# 03_-_MCU_and_Conn.net
KiCad netlist of a schematic drawn in Altium Designer
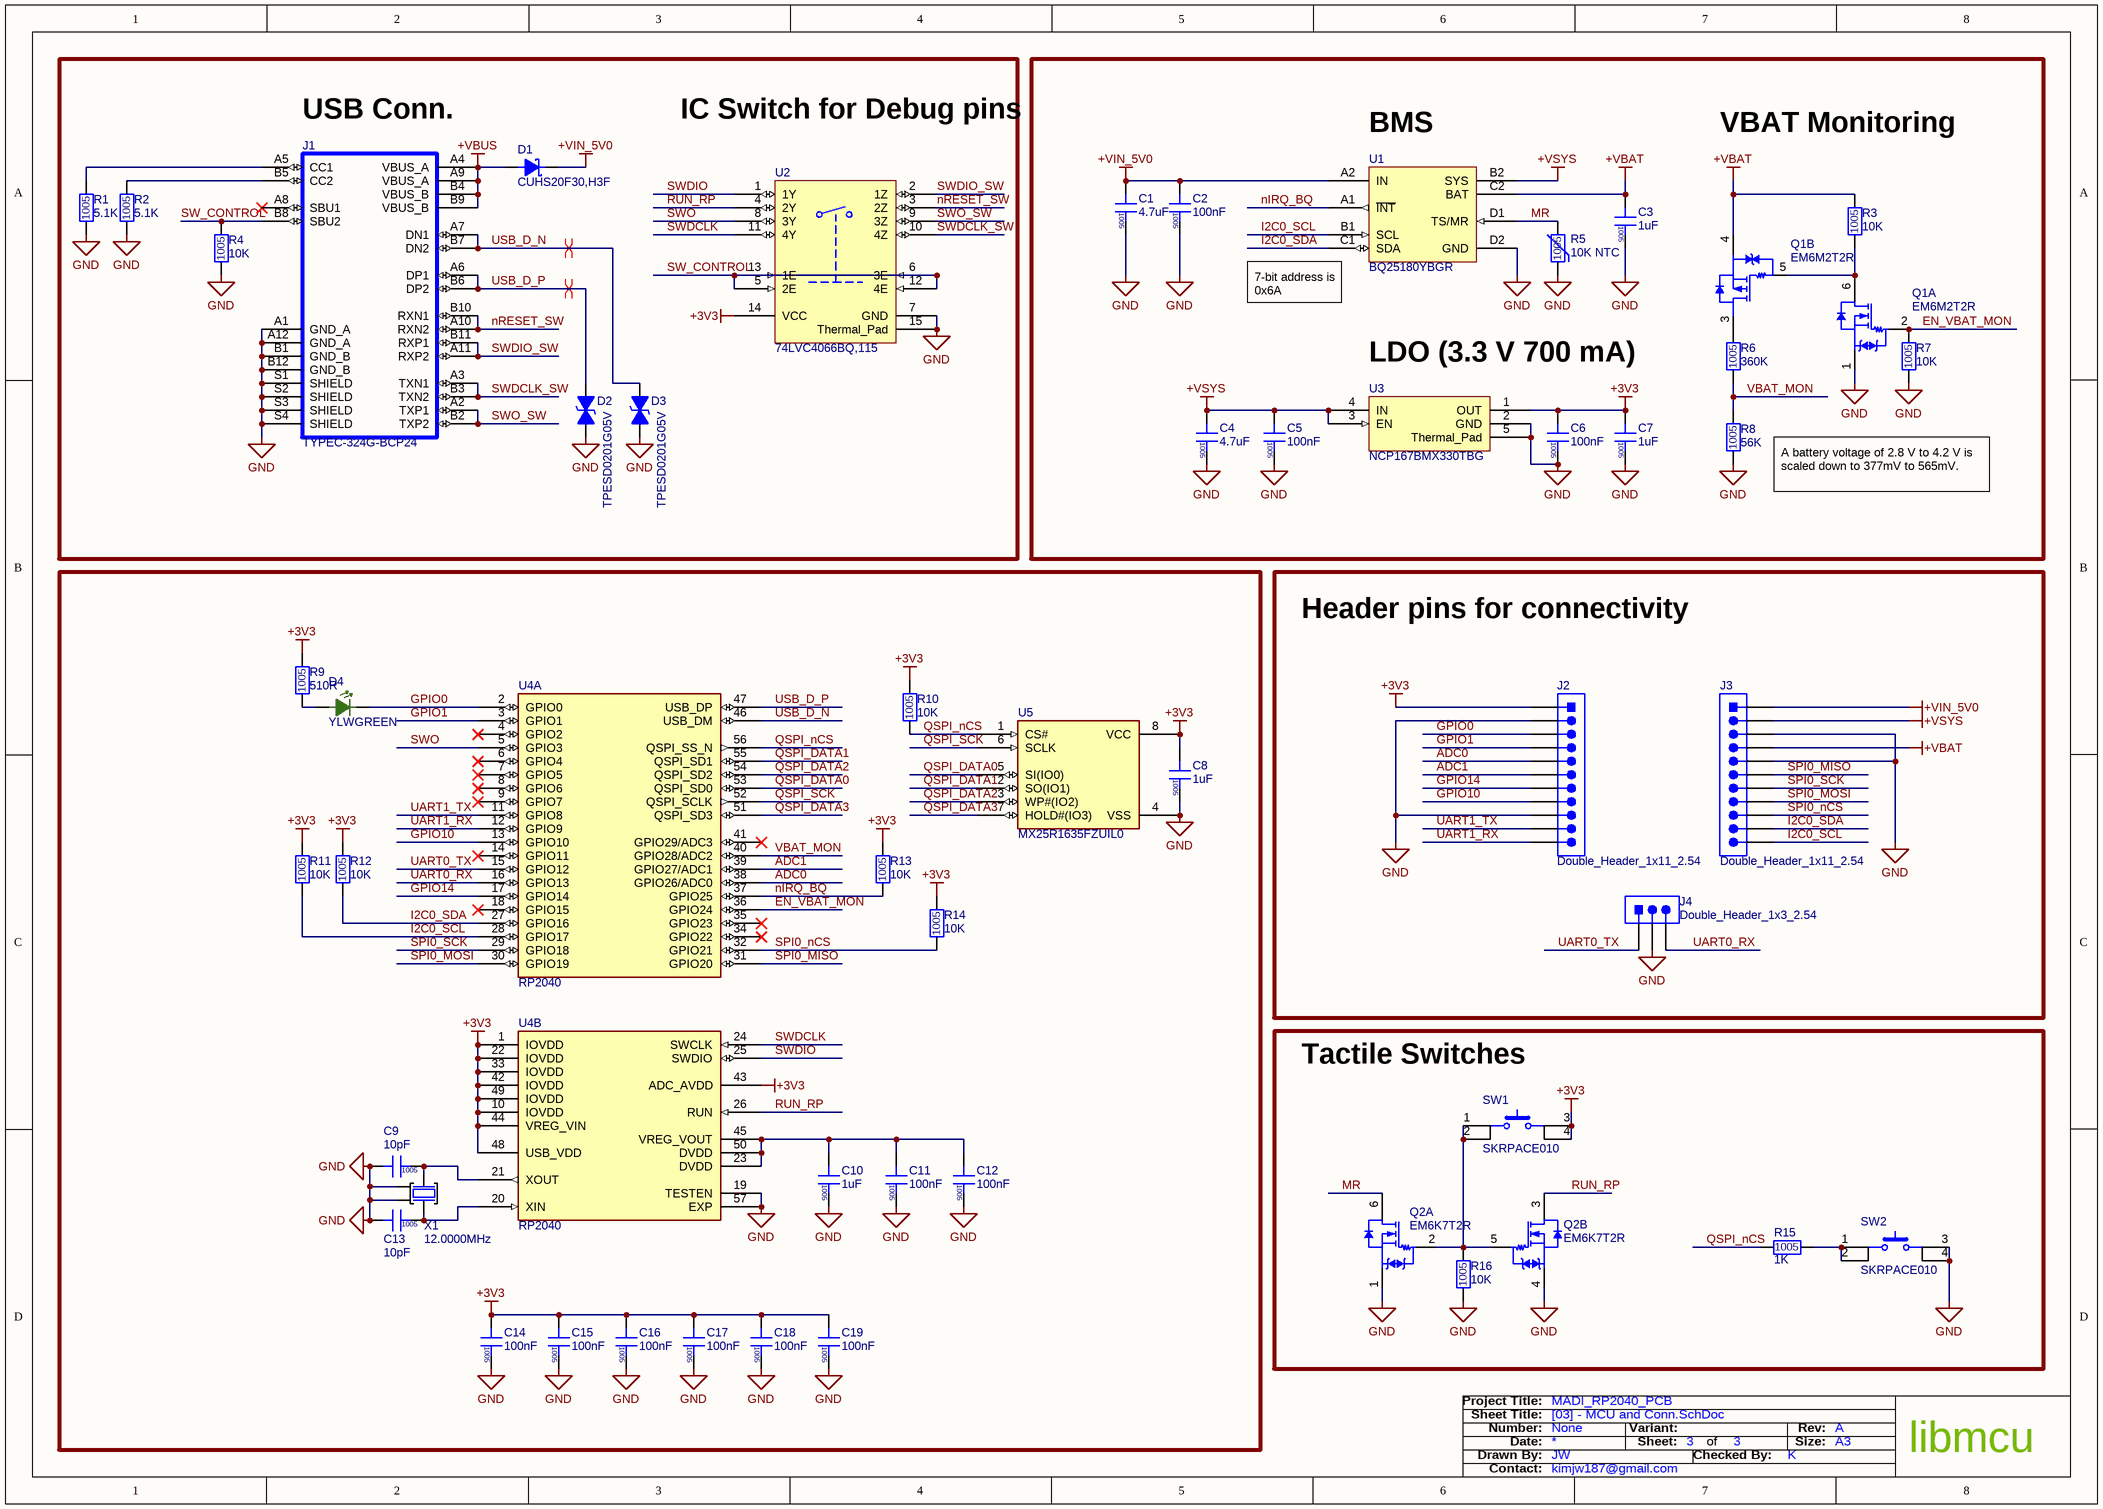
[diagram p0: [03] - MCU and Conn.SchDoc]

(export (version "E")
  (design (tool "Eeschema 10.0.6"))
  (components
    (comp (ref "C1")
      (value "4.7uF")
      (footprint "CAPC1005X06N")
      (description "CAP CER 4.7UF 10V X5R 0402")
      (fields
        (field (name "MANUFACTURER") "Samsung")
        (field (name "MANUFACTURER PART NUMBER") "CL05A475MP5NRNC")
      )
      (libsource (lib "Schlib-master") (part "CL05A475MP5NRNC"))
    )
    (comp (ref "C2")
      (value "100nF")
      (footprint "CAPC1005X06N")
      (description "CAP CER 0.1UF 16V X7R 0402")
      (fields
        (field (name "MANUFACTURER") "Samsung")
        (field (name "MANUFACTURER PART NUMBER") "CL05B104KO5NNNC")
      )
      (libsource (lib "Schlib-master") (part "CL05B104KO5NNNC"))
    )
    (comp (ref "C3")
      (value "1uF")
      (footprint "CAPC1005X06N")
      (description "CAP CER 1UF 16V X5R 0402")
      (fields
        (field (name "MANUFACTURER") "Samsung")
        (field (name "MANUFACTURER PART NUMBER") "CL05A105KO5NNNC")
      )
      (libsource (lib "Schlib-master") (part "CL05A105KO5NNNC"))
    )
    (comp (ref "C4")
      (value "4.7uF")
      (footprint "CAPC1005X06N")
      (description "CAP CER 4.7UF 10V X5R 0402")
      (fields
        (field (name "MANUFACTURER") "Samsung")
        (field (name "MANUFACTURER PART NUMBER") "CL05A475MP5NRNC")
      )
      (libsource (lib "Schlib-master") (part "CL05A475MP5NRNC"))
    )
    (comp (ref "C5")
      (value "100nF")
      (footprint "CAPC1005X06N")
      (description "CAP CER 0.1UF 16V X7R 0402")
      (fields
        (field (name "MANUFACTURER") "Samsung")
        (field (name "MANUFACTURER PART NUMBER") "CL05B104KO5NNNC")
      )
      (libsource (lib "Schlib-master") (part "CL05B104KO5NNNC"))
    )
    (comp (ref "C6")
      (value "100nF")
      (footprint "CAPC1005X06N")
      (description "CAP CER 0.1UF 16V X7R 0402")
      (fields
        (field (name "MANUFACTURER") "Samsung")
        (field (name "MANUFACTURER PART NUMBER") "CL05B104KO5NNNC")
      )
      (libsource (lib "Schlib-master") (part "CL05B104KO5NNNC"))
    )
    (comp (ref "C7")
      (value "1uF")
      (footprint "CAPC1005X06N")
      (description "CAP CER 1UF 16V X5R 0402")
      (fields
        (field (name "MANUFACTURER") "Samsung")
        (field (name "MANUFACTURER PART NUMBER") "CL05A105KO5NNNC")
      )
      (libsource (lib "Schlib-master") (part "CL05A105KO5NNNC"))
    )
    (comp (ref "C8")
      (value "1uF")
      (footprint "CAPC1005X06N")
      (description "CAP CER 1UF 16V X5R 0402")
      (fields
        (field (name "MANUFACTURER") "Samsung")
        (field (name "MANUFACTURER PART NUMBER") "CL05A105KO5NNNC")
      )
      (libsource (lib "Schlib-master") (part "CL05A105KO5NNNC"))
    )
    (comp (ref "C9")
      (value "10pF")
      (footprint "CAPC1005X06N")
      (description "CAP CER 10PF 50V C0G/NP0 0402")
      (fields
        (field (name "MANUFACTURER") "Samsung")
        (field (name "MANUFACTURER PART NUMBER") "CL05C100DB5NNNC")
      )
      (libsource (lib "Schlib-master") (part "CL05C100DB5NNNC"))
    )
    (comp (ref "C10")
      (value "1uF")
      (footprint "CAPC1005X06N")
      (description "CAP CER 1UF 16V X5R 0402")
      (fields
        (field (name "MANUFACTURER") "Samsung")
        (field (name "MANUFACTURER PART NUMBER") "CL05A105KO5NNNC")
      )
      (libsource (lib "Schlib-master") (part "CL05A105KO5NNNC"))
    )
    (comp (ref "C11")
      (value "100nF")
      (footprint "CAPC1005X06N")
      (description "CAP CER 0.1UF 16V X7R 0402")
      (fields
        (field (name "MANUFACTURER") "Samsung")
        (field (name "MANUFACTURER PART NUMBER") "CL05B104KO5NNNC")
      )
      (libsource (lib "Schlib-master") (part "CL05B104KO5NNNC"))
    )
    (comp (ref "C12")
      (value "100nF")
      (footprint "CAPC1005X06N")
      (description "CAP CER 0.1UF 16V X7R 0402")
      (fields
        (field (name "MANUFACTURER") "Samsung")
        (field (name "MANUFACTURER PART NUMBER") "CL05B104KO5NNNC")
      )
      (libsource (lib "Schlib-master") (part "CL05B104KO5NNNC"))
    )
    (comp (ref "C13")
      (value "10pF")
      (footprint "CAPC1005X06N")
      (description "CAP CER 10PF 50V C0G/NP0 0402")
      (fields
        (field (name "MANUFACTURER") "Samsung")
        (field (name "MANUFACTURER PART NUMBER") "CL05C100DB5NNNC")
      )
      (libsource (lib "Schlib-master") (part "CL05C100DB5NNNC"))
    )
    (comp (ref "C14")
      (value "100nF")
      (footprint "CAPC1005X06N")
      (description "CAP CER 0.1UF 16V X7R 0402")
      (fields
        (field (name "MANUFACTURER") "Samsung")
        (field (name "MANUFACTURER PART NUMBER") "CL05B104KO5NNNC")
      )
      (libsource (lib "Schlib-master") (part "CL05B104KO5NNNC"))
    )
    (comp (ref "C15")
      (value "100nF")
      (footprint "CAPC1005X06N")
      (description "CAP CER 0.1UF 16V X7R 0402")
      (fields
        (field (name "MANUFACTURER") "Samsung")
        (field (name "MANUFACTURER PART NUMBER") "CL05B104KO5NNNC")
      )
      (libsource (lib "Schlib-master") (part "CL05B104KO5NNNC"))
    )
    (comp (ref "C16")
      (value "100nF")
      (footprint "CAPC1005X06N")
      (description "CAP CER 0.1UF 16V X7R 0402")
      (fields
        (field (name "MANUFACTURER") "Samsung")
        (field (name "MANUFACTURER PART NUMBER") "CL05B104KO5NNNC")
      )
      (libsource (lib "Schlib-master") (part "CL05B104KO5NNNC"))
    )
    (comp (ref "C17")
      (value "100nF")
      (footprint "CAPC1005X06N")
      (description "CAP CER 0.1UF 16V X7R 0402")
      (fields
        (field (name "MANUFACTURER") "Samsung")
        (field (name "MANUFACTURER PART NUMBER") "CL05B104KO5NNNC")
      )
      (libsource (lib "Schlib-master") (part "CL05B104KO5NNNC"))
    )
    (comp (ref "C18")
      (value "100nF")
      (footprint "CAPC1005X06N")
      (description "CAP CER 0.1UF 16V X7R 0402")
      (fields
        (field (name "MANUFACTURER") "Samsung")
        (field (name "MANUFACTURER PART NUMBER") "CL05B104KO5NNNC")
      )
      (libsource (lib "Schlib-master") (part "CL05B104KO5NNNC"))
    )
    (comp (ref "C19")
      (value "100nF")
      (footprint "CAPC1005X06N")
      (description "CAP CER 0.1UF 16V X7R 0402")
      (fields
        (field (name "MANUFACTURER") "Samsung")
        (field (name "MANUFACTURER PART NUMBER") "CL05B104KO5NNNC")
      )
      (libsource (lib "Schlib-master") (part "CL05B104KO5NNNC"))
    )
    (comp (ref "D1")
      (value "CUHS20F30,H3F")
      (footprint "US2H-DIODE")
      (description "DIODE SCHOTTKY 30V 2A US2H")
      (fields (field (name "MANUFACTURER") "Toshiba"))
      (libsource (lib "Schlib-master") (part "CUHS20F30,H3F"))
    )
    (comp (ref "D2")
      (value "TPESD0201G05V")
      (footprint "DIOC0603X03N")
      (description "TVS DIODE 5.5VWM 40VC 0201")
      (fields (field (name "MANUFACTURER") "TECH PUBLIC"))
      (libsource (lib "Schlib-master") (part "TPESD0201G05V"))
    )
    (comp (ref "D3")
      (value "TPESD0201G05V")
      (footprint "DIOC0603X03N")
      (description "TVS DIODE 5.5VWM 40VC 0201")
      (fields (field (name "MANUFACTURER") "TECH PUBLIC"))
      (libsource (lib "Schlib-master") (part "TPESD0201G05V"))
    )
    (comp (ref "D4")
      (value "YLWGREEN")
      (footprint "LDIOC1608X08N")
      (description "LED YLW/GREEN DIFFUSED 1608 SMD")
      (fields
        (field (name "MANUFACTURER") "Everlight")
        (field (name "MANUFACTURER PART NUMBER") "19-217/G7C-AN1P2/3T")
      )
      (libsource (lib "Schlib-master") (part "19-217/G7C-AN1P2/3T"))
    )
    (comp (ref "J1")
      (value "TYPEC-324G-BCP24")
      (footprint "KUSBX-SMT3-CS-BTR_KYC")
      (description "CONN RCPT USB TYPE C, SMT PINS, TH SHIELD")
      (fields (field (name "MANUFACTURER") "XUNPU"))
      (libsource (lib "Schlib-master") (part "TYPEC-324G-BCP24"))
    )
    (comp (ref "J2")
      (value "Double_Header_1x11_2.54")
      (footprint "1x11_DOUBLE_HEADER_2.54")
      (libsource (lib "Schlib-master") (part "Double_Header_1x11_2.54"))
    )
    (comp (ref "J3")
      (value "Double_Header_1x11_2.54")
      (footprint "1x11_DOUBLE_HEADER_2.54")
      (libsource (lib "") (part "Double_Header_1x11_2.54_1"))
    )
    (comp (ref "J4")
      (value "Double_Header_1x3_2.54")
      (footprint "1x3_DOUBLE_HEADER_2.54")
      (libsource (lib "Schlib-master") (part "Double_Header_1x3_2.54"))
    )
    (comp (ref "Q1")
      (value "EM6M2T2R")
      (footprint "SOTFL50P160X55-6N")
      (description "MOSFET N/P-CH 20V 0.2A EMT6")
      (fields (field (name "MANUFACTURER") "Rohm"))
      (libsource (lib "Schlib-master") (part "EM6M2T2R"))
    )
    (comp (ref "Q2")
      (value "EM6K7T2R")
      (footprint "SOTFL50P160X55-6N")
      (description "MOSFET 2N-CH 20V 0.2A EMT6")
      (fields (field (name "MANUFACTURER") "Rohm"))
      (libsource (lib "Schlib-master") (part "EM6K7T2R"))
    )
    (comp (ref "R1")
      (value "5.1K")
      (footprint "RESC1005X04N")
      (description "RES SMD 5.1K OHM 1% 1/16W 0402")
      (fields
        (field (name "MANUFACTURER") "Yageo")
        (field (name "MANUFACTURER PART NUMBER") "RC0402FR-075K1L")
      )
      (libsource (lib "Schlib-master") (part "RC0402FR-075K1L"))
    )
    (comp (ref "R2")
      (value "5.1K")
      (footprint "RESC1005X04N")
      (description "RES SMD 5.1K OHM 1% 1/16W 0402")
      (fields
        (field (name "MANUFACTURER") "Yageo")
        (field (name "MANUFACTURER PART NUMBER") "RC0402FR-075K1L")
      )
      (libsource (lib "Schlib-master") (part "RC0402FR-075K1L"))
    )
    (comp (ref "R3")
      (value "10K")
      (footprint "RESC1005X04N")
      (description "RES SMD 10K OHM 1% 1/16W 0402")
      (fields
        (field (name "MANUFACTURER") "Yageo")
        (field (name "MANUFACTURER PART NUMBER") "RC0402FR-0710KL")
      )
      (libsource (lib "Schlib-master") (part "RC0402FR-0710KL"))
    )
    (comp (ref "R4")
      (value "10K")
      (footprint "RESC1005X04N")
      (description "RES SMD 10K OHM 1% 1/16W 0402")
      (fields
        (field (name "MANUFACTURER") "Yageo")
        (field (name "MANUFACTURER PART NUMBER") "RC0402FR-0710KL")
      )
      (libsource (lib "Schlib-master") (part "RC0402FR-0710KL"))
    )
    (comp (ref "R5")
      (value "10K NTC")
      (footprint "NTC1005X05N")
      (description "THERMISTOR NTC 10KOHM 3380K 0402")
      (fields
        (field (name "MANUFACTURER") "Murata")
        (field (name "MANUFACTURER PART NUMBER") "NCP15XH103F03RC")
      )
      (libsource (lib "Schlib-master") (part "NCP15XH103F03RC"))
    )
    (comp (ref "R6")
      (value "360K")
      (footprint "RESC1005X04N")
      (description "RES SMD 360K OHM 1% 1/16W 0402")
      (fields
        (field (name "MANUFACTURER") "Yageo")
        (field (name "MANUFACTURER PART NUMBER") "RC0402FR-07360KL")
      )
      (libsource (lib "Schlib-master") (part "RC0402FR-07360KL"))
    )
    (comp (ref "R7")
      (value "10K")
      (footprint "RESC1005X04N")
      (description "RES SMD 10K OHM 1% 1/16W 0402")
      (fields
        (field (name "MANUFACTURER") "Yageo")
        (field (name "MANUFACTURER PART NUMBER") "RC0402FR-0710KL")
      )
      (libsource (lib "Schlib-master") (part "RC0402FR-0710KL"))
    )
    (comp (ref "R8")
      (value "56K")
      (footprint "RESC1005X04N")
      (description "RES SMD 56K OHM 1% 1/16W 0402")
      (fields
        (field (name "MANUFACTURER") "Yageo")
        (field (name "MANUFACTURER PART NUMBER") "RC0402FR-0756KL")
      )
      (libsource (lib "Schlib-master") (part "RC0402FR-0756KL"))
    )
    (comp (ref "R9")
      (value "510R")
      (footprint "RESC1005X04N")
      (description "RES SMD 510 OHM 1% 1/16W 0402")
      (fields (field (name "TOLERANCE") "1%") (field (name "MANUFACTURER") "Yageo"))
      (libsource (lib "Schlib-master") (part "RC0402FR-07510RL"))
    )
    (comp (ref "R10")
      (value "10K")
      (footprint "RESC1005X04N")
      (description "RES SMD 10K OHM 1% 1/16W 0402")
      (fields
        (field (name "MANUFACTURER") "Yageo")
        (field (name "MANUFACTURER PART NUMBER") "RC0402FR-0710KL")
      )
      (libsource (lib "Schlib-master") (part "RC0402FR-0710KL"))
    )
    (comp (ref "R11")
      (value "10K")
      (footprint "RESC1005X04N")
      (description "RES SMD 10K OHM 1% 1/16W 0402")
      (fields
        (field (name "MANUFACTURER") "Yageo")
        (field (name "MANUFACTURER PART NUMBER") "RC0402FR-0710KL")
      )
      (libsource (lib "Schlib-master") (part "RC0402FR-0710KL"))
    )
    (comp (ref "R12")
      (value "10K")
      (footprint "RESC1005X04N")
      (description "RES SMD 10K OHM 1% 1/16W 0402")
      (fields
        (field (name "MANUFACTURER") "Yageo")
        (field (name "MANUFACTURER PART NUMBER") "RC0402FR-0710KL")
      )
      (libsource (lib "Schlib-master") (part "RC0402FR-0710KL"))
    )
    (comp (ref "R13")
      (value "10K")
      (footprint "RESC1005X04N")
      (description "RES SMD 10K OHM 1% 1/16W 0402")
      (fields
        (field (name "MANUFACTURER") "Yageo")
        (field (name "MANUFACTURER PART NUMBER") "RC0402FR-0710KL")
      )
      (libsource (lib "Schlib-master") (part "RC0402FR-0710KL"))
    )
    (comp (ref "R14")
      (value "10K")
      (footprint "RESC1005X04N")
      (description "RES SMD 10K OHM 1% 1/16W 0402")
      (fields
        (field (name "MANUFACTURER") "Yageo")
        (field (name "MANUFACTURER PART NUMBER") "RC0402FR-0710KL")
      )
      (libsource (lib "") (part "RC0402FR-0710KL_1"))
    )
    (comp (ref "R15")
      (value "1K")
      (footprint "RESC1005X04N")
      (description "RES SMD 1K OHM 1% 1/16W 0402")
      (fields
        (field (name "MANUFACTURER") "Yageo")
        (field (name "MANUFACTURER PART NUMBER") "RC0402FR-071KL")
      )
      (libsource (lib "Schlib-master") (part "RC0402FR-071KL"))
    )
    (comp (ref "R16")
      (value "10K")
      (footprint "RESC1005X04N")
      (description "RES SMD 10K OHM 1% 1/16W 0402")
      (fields
        (field (name "MANUFACTURER") "Yageo")
        (field (name "MANUFACTURER PART NUMBER") "RC0402FR-0710KL")
      )
      (libsource (lib "Schlib-master") (part "RC0402FR-0710KL"))
    )
    (comp (ref "SW1")
      (value "SKRPACE010")
      (footprint "PTS810")
      (description "SWITCH TACTILE SPST-NO 0.05A 16V")
      (fields (field (name "MANUFACTURER") "Alps Electric"))
      (libsource (lib "Schlib-master") (part "SKRPACE010"))
    )
    (comp (ref "SW2")
      (value "SKRPACE010")
      (footprint "PTS810")
      (description "SWITCH TACTILE SPST-NO 0.05A 16V")
      (fields (field (name "MANUFACTURER") "Alps Electric"))
      (libsource (lib "Schlib-master") (part "SKRPACE010"))
    )
    (comp (ref "U1")
      (value "BQ25180YBGR")
      (footprint "BGA8C40P2X4_100X155X50_YBG0008")
      (description "IC 1-A LI-ION IC PROGRAMMABLE CHARG")
      (fields (field (name "MANUFACTURER") "Texas Instruments"))
      (libsource (lib "Schlib-master") (part "BQ25180YBGR"))
    )
    (comp (ref "U2")
      (value "74LVC4066BQ,115")
      (footprint "QFN50P250X300X100_HS-15N")
      (description "IC SWITCH QUAD SPST 14DHVQFN")
      (fields (field (name "MANUFACTURER") "Nexperia"))
      (libsource (lib "Schlib-master") (part "74LVC4066BQ,115"))
    )
    (comp (ref "U3")
      (value "NCP167BMX330TBG")
      (footprint "NCP167")
      (description "IC REG LINEAR 3.3V 700MA 4XDFN")
      (fields (field (name "MANUFACTURER") "ON Semiconductor"))
      (libsource (lib "Schlib-master") (part "NCP167BMX330TBG"))
    )
    (comp (ref "U4")
      (value "RP2040")
      (footprint "QFN40P700X700X90_HS-57N_RP2040")
      (description "IC MCU 32BIT EXT MEM 56QFN")
      (fields (field (name "MANUFACTURER") "Raspberry Pi"))
      (libsource (lib "Schlib-master") (part "RP2040"))
    )
    (comp (ref "U5")
      (value "MX25R1635FZUIL0")
      (footprint "USON8_3X2")
      (description "IC FLASH 16MBIT SPI/QUAD 8USON")
      (fields (field (name "MANUFACTURER") "Macronix"))
      (libsource (lib "Schlib-master") (part "MX25R1635FZUIL0"))
    )
    (comp (ref "X1")
      (value "12.0000MHz")
      (footprint "XT2520")
      (description "CRYSTAL 12.0000MHZ 10PF SMD")
      (fields
        (field (name "MANUFACTURER") "Seiko")
        (field (name "MANUFACTURER PART NUMBER") "Q24FA20H0068700")
      )
      (libsource (lib "Schlib-master") (part "Q24FA20H0068700"))
    )
  )
  (nets
    (net (code "1") (name "+3V3") (class "Default")
      (node (ref "C14") (pin "2") (pinfunction "2_2") (pintype "passive"))
      (node (ref "C15") (pin "2") (pinfunction "2_2") (pintype "passive"))
      (node (ref "C16") (pin "2") (pinfunction "2_2") (pintype "passive"))
      (node (ref "C17") (pin "2") (pinfunction "2_2") (pintype "passive"))
      (node (ref "C18") (pin "2") (pinfunction "2_2") (pintype "passive"))
      (node (ref "C19") (pin "2") (pinfunction "2_2") (pintype "passive"))
      (node (ref "C6") (pin "2") (pinfunction "2_2") (pintype "passive"))
      (node (ref "C7") (pin "2") (pinfunction "2_2") (pintype "passive"))
      (node (ref "C8") (pin "2") (pinfunction "2_2") (pintype "passive"))
      (node (ref "J2") (pin "1") (pinfunction "1_1") (pintype "passive"))
      (node (ref "R10") (pin "2") (pinfunction "2_2") (pintype "passive"))
      (node (ref "R11") (pin "2") (pinfunction "2_2") (pintype "passive"))
      (node (ref "R12") (pin "2") (pinfunction "2_2") (pintype "passive"))
      (node (ref "R13") (pin "2") (pinfunction "2_2") (pintype "passive"))
      (node (ref "R14") (pin "2") (pinfunction "2_2") (pintype "passive"))
      (node (ref "R9") (pin "1") (pinfunction "1_1") (pintype "passive"))
      (node (ref "SW1") (pin "3") (pinfunction "2_3") (pintype "passive"))
      (node (ref "SW1") (pin "4") (pinfunction "1_4") (pintype "passive"))
      (node (ref "U2") (pin "14") (pinfunction "VCC_14") (pintype "power_in"))
      (node (ref "U3") (pin "1") (pinfunction "OUT_1") (pintype "power_in"))
      (node (ref "U4") (pin "1") (pinfunction "IOVDD_1") (pintype "power_in"))
      (node (ref "U4") (pin "10") (pinfunction "IOVDD_10") (pintype "power_in"))
      (node (ref "U4") (pin "22") (pinfunction "IOVDD_22") (pintype "power_in"))
      (node (ref "U4") (pin "33") (pinfunction "IOVDD_33") (pintype "power_in"))
      (node (ref "U4") (pin "42") (pinfunction "IOVDD_42") (pintype "power_in"))
      (node (ref "U4") (pin "43") (pinfunction "ADC_AVDD_43") (pintype "power_in"))
      (node (ref "U4") (pin "44") (pinfunction "VREG_VIN_44") (pintype "power_in"))
      (node (ref "U4") (pin "48") (pinfunction "USB_VDD_48") (pintype "power_in"))
      (node (ref "U4") (pin "49") (pinfunction "IOVDD_49") (pintype "power_in"))
      (node (ref "U5") (pin "8") (pinfunction "VCC_8") (pintype "power_in"))
    )
    (net (code "2") (name "+VBAT") (class "Default")
      (node (ref "C3") (pin "2") (pinfunction "2_2") (pintype "passive"))
      (node (ref "J3") (pin "4") (pinfunction "4_4") (pintype "passive"))
      (node (ref "Q1") (pin "4") (pinfunction "S_4") (pintype "passive"))
      (node (ref "R3") (pin "2") (pinfunction "2_2") (pintype "passive"))
      (node (ref "U1") (pin "C2") (pinfunction "BAT_C2") (pintype "power_in"))
    )
    (net (code "3") (name "+VBUS") (class "Default")
      (node (ref "D1") (pin "2") (pinfunction "Anode_2") (pintype "passive"))
      (node (ref "J1") (pin "A4") (pinfunction "VBUS_A_A4") (pintype "power_in"))
      (node (ref "J1") (pin "A9") (pinfunction "VBUS_A_A9") (pintype "power_in"))
      (node (ref "J1") (pin "B4") (pinfunction "VBUS_B_B4") (pintype "power_in"))
      (node (ref "J1") (pin "B9") (pinfunction "VBUS_B_B9") (pintype "power_in"))
    )
    (net (code "4") (name "+VIN_5V0") (class "Default")
      (node (ref "C1") (pin "2") (pinfunction "2_2") (pintype "passive"))
      (node (ref "C2") (pin "2") (pinfunction "2_2") (pintype "passive"))
      (node (ref "D1") (pin "1") (pinfunction "Cathode_1") (pintype "passive"))
      (node (ref "J3") (pin "1") (pinfunction "1_1") (pintype "passive"))
      (node (ref "U1") (pin "A2") (pinfunction "IN_A2") (pintype "power_in"))
    )
    (net (code "5") (name "+VSYS") (class "Default")
      (node (ref "C4") (pin "2") (pinfunction "2_2") (pintype "passive"))
      (node (ref "C5") (pin "2") (pinfunction "2_2") (pintype "passive"))
      (node (ref "J3") (pin "2") (pinfunction "2_2") (pintype "passive"))
      (node (ref "U1") (pin "B2") (pinfunction "SYS_B2") (pintype "power_in"))
      (node (ref "U3") (pin "3") (pinfunction "EN_3") (pintype "input"))
      (node (ref "U3") (pin "4") (pinfunction "IN_4") (pintype "power_in"))
    )
    (net (code "6") (name "/ADC0") (class "Default")
      (node (ref "J2") (pin "5") (pinfunction "5_5") (pintype "passive"))
      (node (ref "U4") (pin "38") (pinfunction "GPIO26/ADC0_38") (pintype "bidirectional"))
    )
    (net (code "7") (name "/ADC1") (class "Default")
      (node (ref "J2") (pin "6") (pinfunction "6_6") (pintype "passive"))
      (node (ref "U4") (pin "39") (pinfunction "GPIO27/ADC1_39") (pintype "bidirectional"))
    )
    (net (code "8") (name "/EN_VBAT_MON") (class "Default")
      (node (ref "Q1") (pin "2") (pinfunction "G_2") (pintype "passive"))
      (node (ref "R7") (pin "2") (pinfunction "2_2") (pintype "passive"))
      (node (ref "U4") (pin "36") (pinfunction "GPIO24_36") (pintype "bidirectional"))
    )
    (net (code "9") (name "/GPIO0") (class "Default")
      (node (ref "D4") (pin "K") (pinfunction "2_K") (pintype "passive"))
      (node (ref "J2") (pin "3") (pinfunction "3_3") (pintype "passive"))
      (node (ref "U4") (pin "2") (pinfunction "GPIO0_2") (pintype "bidirectional"))
    )
    (net (code "10") (name "/GPIO1") (class "Default")
      (node (ref "J2") (pin "4") (pinfunction "4_4") (pintype "passive"))
      (node (ref "U4") (pin "3") (pinfunction "GPIO1_3") (pintype "bidirectional"))
    )
    (net (code "11") (name "/GPIO10") (class "Default")
      (node (ref "J2") (pin "8") (pinfunction "8_8") (pintype "passive"))
      (node (ref "U4") (pin "13") (pinfunction "GPIO10_13") (pintype "bidirectional"))
    )
    (net (code "12") (name "/GPIO14") (class "Default")
      (node (ref "J2") (pin "7") (pinfunction "7_7") (pintype "passive"))
      (node (ref "U4") (pin "17") (pinfunction "GPIO14_17") (pintype "bidirectional"))
    )
    (net (code "13") (name "/I2C0_SCL") (class "Default")
      (node (ref "J3") (pin "11") (pinfunction "11_11") (pintype "passive"))
      (node (ref "R11") (pin "1") (pinfunction "1_1") (pintype "passive"))
      (node (ref "U1") (pin "B1") (pinfunction "SCL_B1") (pintype "input"))
      (node (ref "U4") (pin "28") (pinfunction "GPIO17_28") (pintype "bidirectional"))
    )
    (net (code "14") (name "/I2C0_SDA") (class "Default")
      (node (ref "J3") (pin "10") (pinfunction "10_10") (pintype "passive"))
      (node (ref "R12") (pin "1") (pinfunction "1_1") (pintype "passive"))
      (node (ref "U1") (pin "C1") (pinfunction "SDA_C1") (pintype "bidirectional"))
      (node (ref "U4") (pin "27") (pinfunction "GPIO16_27") (pintype "bidirectional"))
    )
    (net (code "15") (name "/MR") (class "Default")
      (node (ref "Q2") (pin "6") (pinfunction "D_6") (pintype "passive"))
      (node (ref "R5") (pin "2") (pinfunction "2_2") (pintype "passive"))
      (node (ref "U1") (pin "D1") (pinfunction "TS/MR_D1") (pintype "input"))
    )
    (net (code "16") (name "/QSPI_DATA0") (class "Default")
      (node (ref "U4") (pin "53") (pinfunction "QSPI_SD0_53") (pintype "bidirectional"))
      (node (ref "U5") (pin "5") (pinfunction "SI(IO0)_5") (pintype "bidirectional"))
    )
    (net (code "17") (name "/QSPI_DATA1") (class "Default")
      (node (ref "U4") (pin "55") (pinfunction "QSPI_SD1_55") (pintype "bidirectional"))
      (node (ref "U5") (pin "2") (pinfunction "SO(IO1)_2") (pintype "bidirectional"))
    )
    (net (code "18") (name "/QSPI_DATA2") (class "Default")
      (node (ref "U4") (pin "54") (pinfunction "QSPI_SD2_54") (pintype "bidirectional"))
      (node (ref "U5") (pin "3") (pinfunction "WP#(IO2)_3") (pintype "bidirectional"))
    )
    (net (code "19") (name "/QSPI_DATA3") (class "Default")
      (node (ref "U4") (pin "51") (pinfunction "QSPI_SD3_51") (pintype "bidirectional"))
      (node (ref "U5") (pin "7") (pinfunction "HOLD#(IO3)_7") (pintype "bidirectional"))
    )
    (net (code "20") (name "/QSPI_SCK") (class "Default")
      (node (ref "U4") (pin "52") (pinfunction "QSPI_SCLK_52") (pintype "output"))
      (node (ref "U5") (pin "6") (pinfunction "SCLK_6") (pintype "input"))
    )
    (net (code "21") (name "/QSPI_nCS") (class "Default")
      (node (ref "R10") (pin "1") (pinfunction "1_1") (pintype "passive"))
      (node (ref "R15") (pin "1") (pinfunction "1_1") (pintype "passive"))
      (node (ref "U4") (pin "56") (pinfunction "QSPI_SS_N_56") (pintype "output"))
      (node (ref "U5") (pin "1") (pinfunction "CS#_1") (pintype "input"))
    )
    (net (code "22") (name "/RUN_RP") (class "Default")
      (node (ref "Q2") (pin "3") (pinfunction "D_3") (pintype "passive"))
      (node (ref "U2") (pin "4") (pinfunction "2Y_4") (pintype "bidirectional"))
      (node (ref "U4") (pin "26") (pinfunction "RUN_26") (pintype "input"))
    )
    (net (code "23") (name "/SPI0_MISO") (class "Default")
      (node (ref "J3") (pin "6") (pinfunction "6_6") (pintype "passive"))
      (node (ref "U4") (pin "31") (pinfunction "GPIO20_31") (pintype "bidirectional"))
    )
    (net (code "24") (name "/SPI0_MOSI") (class "Default")
      (node (ref "J3") (pin "8") (pinfunction "8_8") (pintype "passive"))
      (node (ref "U4") (pin "30") (pinfunction "GPIO19_30") (pintype "bidirectional"))
    )
    (net (code "25") (name "/SPI0_SCK") (class "Default")
      (node (ref "J3") (pin "7") (pinfunction "7_7") (pintype "passive"))
      (node (ref "U4") (pin "29") (pinfunction "GPIO18_29") (pintype "bidirectional"))
    )
    (net (code "26") (name "/SPI0_nCS") (class "Default")
      (node (ref "J3") (pin "9") (pinfunction "9_9") (pintype "passive"))
      (node (ref "R14") (pin "1") (pinfunction "1_1") (pintype "passive"))
      (node (ref "U4") (pin "32") (pinfunction "GPIO21_32") (pintype "bidirectional"))
    )
    (net (code "27") (name "/SWDCLK") (class "Default")
      (node (ref "U2") (pin "11") (pinfunction "4Y_11") (pintype "bidirectional"))
      (node (ref "U4") (pin "24") (pinfunction "SWCLK_24") (pintype "input"))
    )
    (net (code "28") (name "/SWDCLK_SW") (class "Default")
      (node (ref "J1") (pin "A3") (pinfunction "TXN1_A3") (pintype "bidirectional"))
      (node (ref "J1") (pin "B3") (pinfunction "TXN2_B3") (pintype "bidirectional"))
      (node (ref "U2") (pin "10") (pinfunction "4Z_10") (pintype "bidirectional"))
    )
    (net (code "29") (name "/SWDIO") (class "Default")
      (node (ref "U2") (pin "1") (pinfunction "1Y_1") (pintype "bidirectional"))
      (node (ref "U4") (pin "25") (pinfunction "SWDIO_25") (pintype "bidirectional"))
    )
    (net (code "30") (name "/SWDIO_SW") (class "Default")
      (node (ref "J1") (pin "A11") (pinfunction "RXP2_A11") (pintype "bidirectional"))
      (node (ref "J1") (pin "B11") (pinfunction "RXP1_B11") (pintype "bidirectional"))
      (node (ref "U2") (pin "2") (pinfunction "1Z_2") (pintype "bidirectional"))
    )
    (net (code "31") (name "/SWO") (class "Default")
      (node (ref "U2") (pin "8") (pinfunction "3Y_8") (pintype "bidirectional"))
      (node (ref "U4") (pin "5") (pinfunction "GPIO3_5") (pintype "bidirectional"))
    )
    (net (code "32") (name "/SWO_SW") (class "Default")
      (node (ref "J1") (pin "A2") (pinfunction "TXP1_A2") (pintype "bidirectional"))
      (node (ref "J1") (pin "B2") (pinfunction "TXP2_B2") (pintype "bidirectional"))
      (node (ref "U2") (pin "9") (pinfunction "3Z_9") (pintype "bidirectional"))
    )
    (net (code "33") (name "/SW_CONTROL") (class "Default")
      (node (ref "J1") (pin "B8") (pinfunction "SBU2_B8") (pintype "bidirectional"))
      (node (ref "R4") (pin "2") (pinfunction "2_2") (pintype "passive"))
      (node (ref "U2") (pin "12") (pinfunction "4E_12") (pintype "input"))
      (node (ref "U2") (pin "13") (pinfunction "1E_13") (pintype "input"))
      (node (ref "U2") (pin "5") (pinfunction "2E_5") (pintype "input"))
      (node (ref "U2") (pin "6") (pinfunction "3E_6") (pintype "input"))
    )
    (net (code "34") (name "/UART0_RX") (class "Default")
      (node (ref "J4") (pin "3") (pinfunction "3_3") (pintype "passive"))
      (node (ref "U4") (pin "16") (pinfunction "GPIO13_16") (pintype "bidirectional"))
    )
    (net (code "35") (name "/UART0_TX") (class "Default")
      (node (ref "J4") (pin "1") (pinfunction "1_1") (pintype "passive"))
      (node (ref "U4") (pin "15") (pinfunction "GPIO12_15") (pintype "bidirectional"))
    )
    (net (code "36") (name "/UART1_RX") (class "Default")
      (node (ref "J2") (pin "11") (pinfunction "11_11") (pintype "passive"))
      (node (ref "U4") (pin "12") (pinfunction "GPIO9_12") (pintype "bidirectional"))
    )
    (net (code "37") (name "/UART1_TX") (class "Default")
      (node (ref "J2") (pin "10") (pinfunction "10_10") (pintype "passive"))
      (node (ref "U4") (pin "11") (pinfunction "GPIO8_11") (pintype "bidirectional"))
    )
    (net (code "38") (name "/USB_D_N") (class "Default")
      (node (ref "D3") (pin "1") (pinfunction "1_1") (pintype "passive"))
      (node (ref "J1") (pin "A7") (pinfunction "DN1_A7") (pintype "bidirectional"))
      (node (ref "J1") (pin "B7") (pinfunction "DN2_B7") (pintype "bidirectional"))
      (node (ref "U4") (pin "46") (pinfunction "USB_DM_46") (pintype "bidirectional"))
    )
    (net (code "39") (name "/USB_D_P") (class "Default")
      (node (ref "D2") (pin "1") (pinfunction "1_1") (pintype "passive"))
      (node (ref "J1") (pin "A6") (pinfunction "DP1_A6") (pintype "bidirectional"))
      (node (ref "J1") (pin "B6") (pinfunction "DP2_B6") (pintype "bidirectional"))
      (node (ref "U4") (pin "47") (pinfunction "USB_DP_47") (pintype "bidirectional"))
    )
    (net (code "40") (name "/VBAT_MON") (class "Default")
      (node (ref "R6") (pin "1") (pinfunction "1_1") (pintype "passive"))
      (node (ref "R8") (pin "2") (pinfunction "2_2") (pintype "passive"))
      (node (ref "U4") (pin "40") (pinfunction "GPIO28/ADC2_40") (pintype "bidirectional"))
    )
    (net (code "41") (name "/nIRQ_BQ") (class "Default")
      (node (ref "R13") (pin "1") (pinfunction "1_1") (pintype "passive"))
      (node (ref "U1") (pin "A1") (pinfunction "~{INT}_A1") (pintype "output"))
      (node (ref "U4") (pin "37") (pinfunction "GPIO25_37") (pintype "bidirectional"))
    )
    (net (code "42") (name "/nRESET_SW") (class "Default")
      (node (ref "J1") (pin "A10") (pinfunction "RXN2_A10") (pintype "bidirectional"))
      (node (ref "J1") (pin "B10") (pinfunction "RXN1_B10") (pintype "bidirectional"))
      (node (ref "U2") (pin "3") (pinfunction "2Z_3") (pintype "bidirectional"))
    )
    (net (code "43") (name "GND") (class "Default")
      (node (ref "C1") (pin "1") (pinfunction "1_1") (pintype "passive"))
      (node (ref "C10") (pin "1") (pinfunction "1_1") (pintype "passive"))
      (node (ref "C11") (pin "1") (pinfunction "1_1") (pintype "passive"))
      (node (ref "C12") (pin "1") (pinfunction "1_1") (pintype "passive"))
      (node (ref "C13") (pin "2") (pinfunction "2_2") (pintype "passive"))
      (node (ref "C14") (pin "1") (pinfunction "1_1") (pintype "passive"))
      (node (ref "C15") (pin "1") (pinfunction "1_1") (pintype "passive"))
      (node (ref "C16") (pin "1") (pinfunction "1_1") (pintype "passive"))
      (node (ref "C17") (pin "1") (pinfunction "1_1") (pintype "passive"))
      (node (ref "C18") (pin "1") (pinfunction "1_1") (pintype "passive"))
      (node (ref "C19") (pin "1") (pinfunction "1_1") (pintype "passive"))
      (node (ref "C2") (pin "1") (pinfunction "1_1") (pintype "passive"))
      (node (ref "C3") (pin "1") (pinfunction "1_1") (pintype "passive"))
      (node (ref "C4") (pin "1") (pinfunction "1_1") (pintype "passive"))
      (node (ref "C5") (pin "1") (pinfunction "1_1") (pintype "passive"))
      (node (ref "C6") (pin "1") (pinfunction "1_1") (pintype "passive"))
      (node (ref "C7") (pin "1") (pinfunction "1_1") (pintype "passive"))
      (node (ref "C8") (pin "1") (pinfunction "1_1") (pintype "passive"))
      (node (ref "C9") (pin "2") (pinfunction "2_2") (pintype "passive"))
      (node (ref "D2") (pin "2") (pinfunction "2_2") (pintype "passive"))
      (node (ref "D3") (pin "2") (pinfunction "2_2") (pintype "passive"))
      (node (ref "J1") (pin "A1") (pinfunction "GND_A_A1") (pintype "power_in"))
      (node (ref "J1") (pin "A12") (pinfunction "GND_A_A12") (pintype "power_in"))
      (node (ref "J1") (pin "B1") (pinfunction "GND_B_B1") (pintype "power_in"))
      (node (ref "J1") (pin "B12") (pinfunction "GND_B_B12") (pintype "power_in"))
      (node (ref "J1") (pin "S1") (pinfunction "SHIELD_S1") (pintype "passive"))
      (node (ref "J1") (pin "S2") (pinfunction "SHIELD_S2") (pintype "passive"))
      (node (ref "J1") (pin "S3") (pinfunction "SHIELD_S3") (pintype "passive"))
      (node (ref "J1") (pin "S4") (pinfunction "SHIELD_S4") (pintype "passive"))
      (node (ref "J2") (pin "2") (pinfunction "2_2") (pintype "passive"))
      (node (ref "J2") (pin "9") (pinfunction "9_9") (pintype "passive"))
      (node (ref "J3") (pin "3") (pinfunction "3_3") (pintype "passive"))
      (node (ref "J3") (pin "5") (pinfunction "5_5") (pintype "passive"))
      (node (ref "J4") (pin "2") (pinfunction "2_2") (pintype "passive"))
      (node (ref "Q1") (pin "1") (pinfunction "S_1") (pintype "passive"))
      (node (ref "Q2") (pin "1") (pinfunction "S_1") (pintype "passive"))
      (node (ref "Q2") (pin "4") (pinfunction "S_4") (pintype "passive"))
      (node (ref "R1") (pin "1") (pinfunction "1_1") (pintype "passive"))
      (node (ref "R16") (pin "1") (pinfunction "1_1") (pintype "passive"))
      (node (ref "R2") (pin "1") (pinfunction "1_1") (pintype "passive"))
      (node (ref "R4") (pin "1") (pinfunction "1_1") (pintype "passive"))
      (node (ref "R5") (pin "1") (pinfunction "1_1") (pintype "passive"))
      (node (ref "R7") (pin "1") (pinfunction "1_1") (pintype "passive"))
      (node (ref "R8") (pin "1") (pinfunction "1_1") (pintype "passive"))
      (node (ref "SW2") (pin "3") (pinfunction "2_3") (pintype "passive"))
      (node (ref "SW2") (pin "4") (pinfunction "1_4") (pintype "passive"))
      (node (ref "U1") (pin "D2") (pinfunction "GND_D2") (pintype "power_in"))
      (node (ref "U2") (pin "15") (pinfunction "Thermal_Pad_15") (pintype "power_in"))
      (node (ref "U2") (pin "7") (pinfunction "GND_7") (pintype "power_in"))
      (node (ref "U3") (pin "2") (pinfunction "GND_2") (pintype "power_in"))
      (node (ref "U3") (pin "5") (pinfunction "Thermal_Pad_5") (pintype "passive"))
      (node (ref "U4") (pin "19") (pinfunction "TESTEN_19") (pintype "passive"))
      (node (ref "U4") (pin "57") (pinfunction "EXP_57") (pintype "power_in"))
      (node (ref "U5") (pin "4") (pinfunction "VSS_4") (pintype "power_in"))
      (node (ref "X1") (pin "2") (pinfunction "GND_2") (pintype "passive"))
      (node (ref "X1") (pin "4") (pinfunction "GND_4") (pintype "passive"))
    )
    (net (code "44") (name "Net-(D4-1)") (class "Default")
      (node (ref "D4") (pin "A") (pinfunction "1_A") (pintype "passive"))
      (node (ref "R9") (pin "2") (pinfunction "2_2") (pintype "passive"))
    )
    (net (code "45") (name "Net-(J1-CC1)") (class "Default")
      (node (ref "J1") (pin "A5") (pinfunction "CC1_A5") (pintype "bidirectional"))
      (node (ref "R1") (pin "2") (pinfunction "2_2") (pintype "passive"))
    )
    (net (code "46") (name "Net-(J1-CC2)") (class "Default")
      (node (ref "J1") (pin "B5") (pinfunction "CC2_B5") (pintype "bidirectional"))
      (node (ref "R2") (pin "2") (pinfunction "2_2") (pintype "passive"))
    )
    (net (code "47") (name "Net-(Q1A-D)") (class "Default")
      (node (ref "Q1") (pin "5") (pinfunction "G_5") (pintype "passive"))
      (node (ref "Q1") (pin "6") (pinfunction "D_6") (pintype "passive"))
      (node (ref "R3") (pin "1") (pinfunction "1_1") (pintype "passive"))
    )
    (net (code "48") (name "Net-(Q1B-D)") (class "Default")
      (node (ref "Q1") (pin "3") (pinfunction "D_3") (pintype "passive"))
      (node (ref "R6") (pin "2") (pinfunction "2_2") (pintype "passive"))
    )
    (net (code "49") (name "Net-(Q2A-G)") (class "Default")
      (node (ref "Q2") (pin "2") (pinfunction "G_2") (pintype "passive"))
      (node (ref "Q2") (pin "5") (pinfunction "G_5") (pintype "passive"))
      (node (ref "R16") (pin "2") (pinfunction "2_2") (pintype "passive"))
      (node (ref "SW1") (pin "1") (pinfunction "1_1") (pintype "passive"))
      (node (ref "SW1") (pin "2") (pinfunction "2_2") (pintype "passive"))
    )
    (net (code "50") (name "Net-(R15-Pad2)") (class "Default")
      (node (ref "R15") (pin "2") (pinfunction "2_2") (pintype "passive"))
      (node (ref "SW2") (pin "1") (pinfunction "1_1") (pintype "passive"))
      (node (ref "SW2") (pin "2") (pinfunction "2_2") (pintype "passive"))
    )
    (net (code "51") (name "Net-(U4B-VREG_VOUT)") (class "Default")
      (node (ref "C10") (pin "2") (pinfunction "2_2") (pintype "passive"))
      (node (ref "C11") (pin "2") (pinfunction "2_2") (pintype "passive"))
      (node (ref "C12") (pin "2") (pinfunction "2_2") (pintype "passive"))
      (node (ref "U4") (pin "23") (pinfunction "DVDD_23") (pintype "power_in"))
      (node (ref "U4") (pin "45") (pinfunction "VREG_VOUT_45") (pintype "power_in"))
      (node (ref "U4") (pin "50") (pinfunction "DVDD_50") (pintype "power_in"))
    )
    (net (code "52") (name "Net-(U4B-XIN)") (class "Default")
      (node (ref "C13") (pin "1") (pinfunction "1_1") (pintype "passive"))
      (node (ref "U4") (pin "20") (pinfunction "XIN_20") (pintype "input"))
      (node (ref "X1") (pin "3") (pinfunction "OUT_3") (pintype "passive"))
    )
    (net (code "53") (name "Net-(U4B-XOUT)") (class "Default")
      (node (ref "C9") (pin "1") (pinfunction "1_1") (pintype "passive"))
      (node (ref "U4") (pin "21") (pinfunction "XOUT_21") (pintype "output"))
      (node (ref "X1") (pin "1") (pinfunction "IN_1") (pintype "passive"))
    )
    (net (code "54") (name "unconnected-(J1-SBU1-PadA8)") (class "Default")
      (node (ref "J1") (pin "A8") (pinfunction "SBU1_A8") (pintype "bidirectional+no_connect"))
    )
    (net (code "55") (name "unconnected-(U4A-GPIO2-Pad4)") (class "Default")
      (node (ref "U4") (pin "4") (pinfunction "GPIO2_4") (pintype "bidirectional+no_connect"))
    )
    (net (code "56") (name "unconnected-(U4A-GPIO4-Pad6)") (class "Default")
      (node (ref "U4") (pin "6") (pinfunction "GPIO4_6") (pintype "bidirectional+no_connect"))
    )
    (net (code "57") (name "unconnected-(U4A-GPIO5-Pad7)") (class "Default")
      (node (ref "U4") (pin "7") (pinfunction "GPIO5_7") (pintype "bidirectional+no_connect"))
    )
    (net (code "58") (name "unconnected-(U4A-GPIO6-Pad8)") (class "Default")
      (node (ref "U4") (pin "8") (pinfunction "GPIO6_8") (pintype "bidirectional+no_connect"))
    )
    (net (code "59") (name "unconnected-(U4A-GPIO7-Pad9)") (class "Default")
      (node (ref "U4") (pin "9") (pinfunction "GPIO7_9") (pintype "bidirectional+no_connect"))
    )
    (net (code "60") (name "unconnected-(U4A-GPIO11-Pad14)") (class "Default")
      (node (ref "U4") (pin "14") (pinfunction "GPIO11_14") (pintype "bidirectional+no_connect"))
    )
    (net (code "61") (name "unconnected-(U4A-GPIO15-Pad18)") (class "Default")
      (node (ref "U4") (pin "18") (pinfunction "GPIO15_18") (pintype "bidirectional+no_connect"))
    )
    (net (code "62") (name "unconnected-(U4A-GPIO22-Pad34)") (class "Default")
      (node (ref "U4") (pin "34") (pinfunction "GPIO22_34") (pintype "bidirectional+no_connect"))
    )
    (net (code "63") (name "unconnected-(U4A-GPIO23-Pad35)") (class "Default")
      (node (ref "U4") (pin "35") (pinfunction "GPIO23_35") (pintype "bidirectional+no_connect"))
    )
    (net (code "64") (name "unconnected-(U4A-GPIO29{slash}ADC3-Pad41)") (class "Default")
      (node (ref "U4") (pin "41") (pinfunction "GPIO29/ADC3_41") (pintype "bidirectional+no_connect"))
    )
  )
)
